# Alimentation.net
KiCad netlist of a schematic drawn in EAGLE
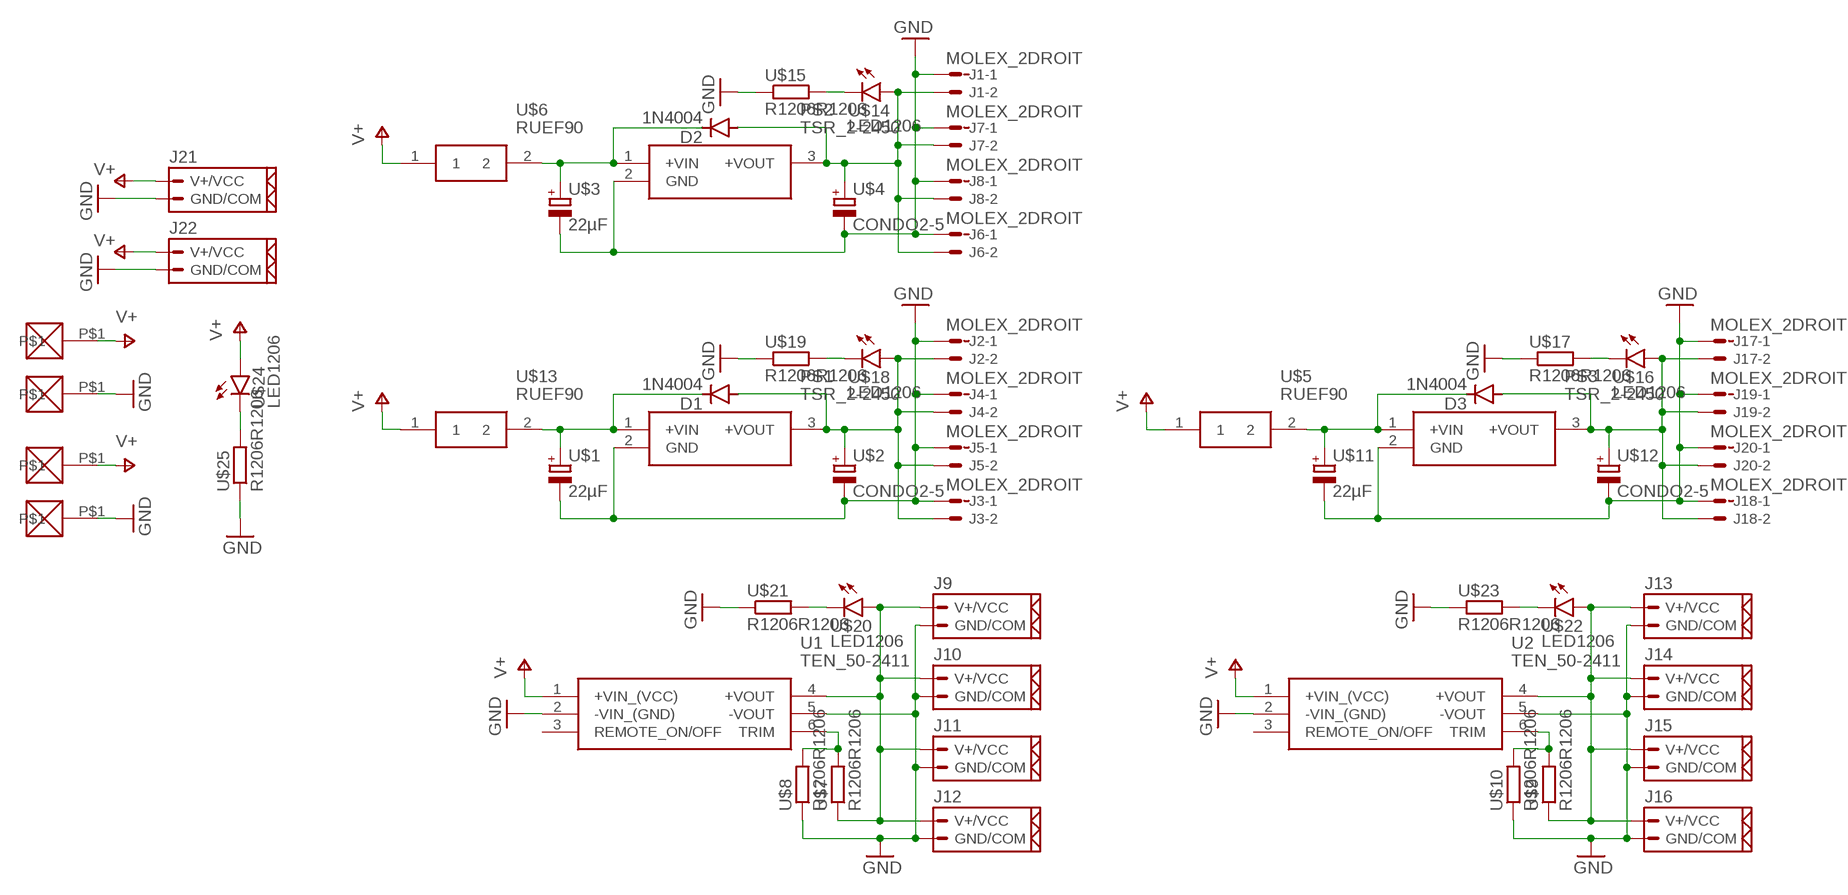
[diagram p0: schematic, sheet 1]

(export (version "E")
  (design (tool "Eeschema 10.0.6"))
  (components
    (comp (ref "D1")
      (value "1N4004")
      (footprint "eagle-import:DO41-10")
      (libsource (lib "eagle-import") (part "1N4004"))
    )
    (comp (ref "D2")
      (value "1N4004")
      (footprint "eagle-import:DO41-10")
      (libsource (lib "eagle-import") (part "1N4004"))
    )
    (comp (ref "D3")
      (value "1N4004")
      (footprint "eagle-import:DO41-10")
      (libsource (lib "eagle-import") (part "1N4004"))
    )
    (comp (ref "J1")
      (value "MOLEX_2DROIT")
      (footprint "eagle-import:CON_2_DROIT")
      (fields (field (name "MF") "MOLEX"))
      (libsource (lib "eagle-import") (part "MOLEX_2DROIT"))
    )
    (comp (ref "J2")
      (value "MOLEX_2DROIT")
      (footprint "eagle-import:CON_2_DROIT")
      (fields (field (name "MF") "MOLEX"))
      (libsource (lib "eagle-import") (part "MOLEX_2DROIT"))
    )
    (comp (ref "J3")
      (value "MOLEX_2DROIT")
      (footprint "eagle-import:CON_2_DROIT")
      (fields (field (name "MF") "MOLEX"))
      (libsource (lib "eagle-import") (part "MOLEX_2DROIT"))
    )
    (comp (ref "J4")
      (value "MOLEX_2DROIT")
      (footprint "eagle-import:CON_2_DROIT")
      (fields (field (name "MF") "MOLEX"))
      (libsource (lib "eagle-import") (part "MOLEX_2DROIT"))
    )
    (comp (ref "J5")
      (value "MOLEX_2DROIT")
      (footprint "eagle-import:CON_2_DROIT")
      (fields (field (name "MF") "MOLEX"))
      (libsource (lib "eagle-import") (part "MOLEX_2DROIT"))
    )
    (comp (ref "J6")
      (value "MOLEX_2DROIT")
      (footprint "eagle-import:CON_2_DROIT")
      (fields (field (name "MF") "MOLEX"))
      (libsource (lib "eagle-import") (part "MOLEX_2DROIT"))
    )
    (comp (ref "J7")
      (value "MOLEX_2DROIT")
      (footprint "eagle-import:CON_2_DROIT")
      (fields (field (name "MF") "MOLEX"))
      (libsource (lib "eagle-import") (part "MOLEX_2DROIT"))
    )
    (comp (ref "J8")
      (value "MOLEX_2DROIT")
      (footprint "eagle-import:CON_2_DROIT")
      (fields (field (name "MF") "MOLEX"))
      (libsource (lib "eagle-import") (part "MOLEX_2DROIT"))
    )
    (comp (ref "J9")
      (value "MOLEX_2_PUISSDROIT")
      (footprint "eagle-import:CON_2_PUISS_DROIT")
      (libsource (lib "eagle-import") (part "MOLEX_2_PUISSDROIT"))
    )
    (comp (ref "J10")
      (value "MOLEX_2_PUISSDROIT")
      (footprint "eagle-import:CON_2_PUISS_DROIT")
      (libsource (lib "eagle-import") (part "MOLEX_2_PUISSDROIT"))
    )
    (comp (ref "J11")
      (value "MOLEX_2_PUISS90°")
      (footprint "eagle-import:CON_2_PUISS_90°")
      (libsource (lib "eagle-import") (part "MOLEX_2_PUISS90°"))
    )
    (comp (ref "J12")
      (value "MOLEX_2_PUISS90°")
      (footprint "eagle-import:CON_2_PUISS_90°")
      (libsource (lib "eagle-import") (part "MOLEX_2_PUISS90°"))
    )
    (comp (ref "J13")
      (value "MOLEX_2_PUISSDROIT")
      (footprint "eagle-import:CON_2_PUISS_DROIT")
      (libsource (lib "eagle-import") (part "MOLEX_2_PUISSDROIT"))
    )
    (comp (ref "J14")
      (value "MOLEX_2_PUISSDROIT")
      (footprint "eagle-import:CON_2_PUISS_DROIT")
      (libsource (lib "eagle-import") (part "MOLEX_2_PUISSDROIT"))
    )
    (comp (ref "J15")
      (value "MOLEX_2_PUISS90°")
      (footprint "eagle-import:CON_2_PUISS_90°")
      (libsource (lib "eagle-import") (part "MOLEX_2_PUISS90°"))
    )
    (comp (ref "J16")
      (value "MOLEX_2_PUISS90°")
      (footprint "eagle-import:CON_2_PUISS_90°")
      (libsource (lib "eagle-import") (part "MOLEX_2_PUISS90°"))
    )
    (comp (ref "J17")
      (value "MOLEX_2DROIT")
      (footprint "eagle-import:CON_2_DROIT")
      (fields (field (name "MF") "MOLEX"))
      (libsource (lib "eagle-import") (part "MOLEX_2DROIT"))
    )
    (comp (ref "J18")
      (value "MOLEX_2DROIT")
      (footprint "eagle-import:CON_2_DROIT")
      (fields (field (name "MF") "MOLEX"))
      (libsource (lib "eagle-import") (part "MOLEX_2DROIT"))
    )
    (comp (ref "J19")
      (value "MOLEX_2DROIT")
      (footprint "eagle-import:CON_2_DROIT")
      (fields (field (name "MF") "MOLEX"))
      (libsource (lib "eagle-import") (part "MOLEX_2DROIT"))
    )
    (comp (ref "J20")
      (value "MOLEX_2DROIT")
      (footprint "eagle-import:CON_2_DROIT")
      (fields (field (name "MF") "MOLEX"))
      (libsource (lib "eagle-import") (part "MOLEX_2DROIT"))
    )
    (comp (ref "J21")
      (value "MOLEX_2_PUISS90°")
      (footprint "eagle-import:CON_2_PUISS_90°")
      (libsource (lib "eagle-import") (part "MOLEX_2_PUISS90°"))
    )
    (comp (ref "J22")
      (value "MOLEX_2_PUISS90°")
      (footprint "eagle-import:CON_2_PUISS_90°")
      (libsource (lib "eagle-import") (part "MOLEX_2_PUISS90°"))
    )
    (comp (ref "PS1")
      (value "TSR_2-2450")
      (footprint "eagle-import:TSR-2")
      (fields
        (field (name "MANUFACTURER_PART_NUMBER") "TSR 2-2450")
        (field (name "MOUSER_PART_NUMBER") "495-TSR2-2450")
        (field (name "RS_PART_NUMBER") "1666063")
      )
      (libsource (lib "eagle-import") (part "TSR_2-2450"))
    )
    (comp (ref "PS2")
      (value "TSR_2-2450")
      (footprint "eagle-import:TSR-2")
      (fields
        (field (name "MANUFACTURER_PART_NUMBER") "TSR 2-2450")
        (field (name "MOUSER_PART_NUMBER") "495-TSR2-2450")
        (field (name "RS_PART_NUMBER") "1666063")
      )
      (libsource (lib "eagle-import") (part "TSR_2-2450"))
    )
    (comp (ref "PS3")
      (value "TSR_2-2450")
      (footprint "eagle-import:TSR-2")
      (fields
        (field (name "MANUFACTURER_PART_NUMBER") "TSR 2-2450")
        (field (name "MOUSER_PART_NUMBER") "495-TSR2-2450")
        (field (name "RS_PART_NUMBER") "1666063")
      )
      (libsource (lib "eagle-import") (part "TSR_2-2450"))
    )
    (comp (ref "U$1")
      (value "22µF")
      (footprint "eagle-import:E2-5")
      (libsource (lib "eagle-import") (part "CONDO2-5"))
    )
    (comp (ref "U$2")
      (value "CONDO2-5")
      (footprint "eagle-import:E2-5")
      (libsource (lib "eagle-import") (part "CONDO2-5"))
    )
    (comp (ref "U$3")
      (value "22µF")
      (footprint "eagle-import:E2-5")
      (libsource (lib "eagle-import") (part "CONDO2-5"))
    )
    (comp (ref "U$4")
      (value "CONDO2-5")
      (footprint "eagle-import:E2-5")
      (libsource (lib "eagle-import") (part "CONDO2-5"))
    )
    (comp (ref "U$5")
      (value "RUEF90")
      (footprint "eagle-import:RUEF090")
      (libsource (lib "eagle-import") (part "RUEF90"))
    )
    (comp (ref "U$6")
      (value "RUEF90")
      (footprint "eagle-import:RUEF090")
      (libsource (lib "eagle-import") (part "RUEF90"))
    )
    (comp (ref "U$7")
      (value "R1206R1206")
      (footprint "eagle-import:R1206")
      (libsource (lib "eagle-import") (part "R1206R1206"))
    )
    (comp (ref "U$8")
      (value "R1206R1206")
      (footprint "eagle-import:R1206")
      (libsource (lib "eagle-import") (part "R1206R1206"))
    )
    (comp (ref "U$9")
      (value "R1206R1206")
      (footprint "eagle-import:R1206")
      (libsource (lib "eagle-import") (part "R1206R1206"))
    )
    (comp (ref "U$10")
      (value "R1206R1206")
      (footprint "eagle-import:R1206")
      (libsource (lib "eagle-import") (part "R1206R1206"))
    )
    (comp (ref "U$11")
      (value "22µF")
      (footprint "eagle-import:E2-5")
      (libsource (lib "eagle-import") (part "CONDO2-5"))
    )
    (comp (ref "U$12")
      (value "CONDO2-5")
      (footprint "eagle-import:E2-5")
      (libsource (lib "eagle-import") (part "CONDO2-5"))
    )
    (comp (ref "U$13")
      (value "RUEF90")
      (footprint "eagle-import:RUEF090")
      (libsource (lib "eagle-import") (part "RUEF90"))
    )
    (comp (ref "U$14")
      (value "LED1206")
      (footprint "eagle-import:1206")
      (libsource (lib "eagle-import") (part "LED1206"))
    )
    (comp (ref "U$15")
      (value "R1206R1206")
      (footprint "eagle-import:R1206")
      (libsource (lib "eagle-import") (part "R1206R1206"))
    )
    (comp (ref "U$16")
      (value "LED1206")
      (footprint "eagle-import:1206")
      (libsource (lib "eagle-import") (part "LED1206"))
    )
    (comp (ref "U$17")
      (value "R1206R1206")
      (footprint "eagle-import:R1206")
      (libsource (lib "eagle-import") (part "R1206R1206"))
    )
    (comp (ref "U$18")
      (value "LED1206")
      (footprint "eagle-import:1206")
      (libsource (lib "eagle-import") (part "LED1206"))
    )
    (comp (ref "U$19")
      (value "R1206R1206")
      (footprint "eagle-import:R1206")
      (libsource (lib "eagle-import") (part "R1206R1206"))
    )
    (comp (ref "U$20")
      (value "LED1206")
      (footprint "eagle-import:1206")
      (libsource (lib "eagle-import") (part "LED1206"))
    )
    (comp (ref "U$21")
      (value "R1206R1206")
      (footprint "eagle-import:R1206")
      (libsource (lib "eagle-import") (part "R1206R1206"))
    )
    (comp (ref "U$22")
      (value "LED1206")
      (footprint "eagle-import:1206")
      (libsource (lib "eagle-import") (part "LED1206"))
    )
    (comp (ref "U$23")
      (value "R1206R1206")
      (footprint "eagle-import:R1206")
      (libsource (lib "eagle-import") (part "R1206R1206"))
    )
    (comp (ref "U$24")
      (value "LED1206")
      (footprint "eagle-import:1206")
      (libsource (lib "eagle-import") (part "LED1206"))
    )
    (comp (ref "U$25")
      (value "R1206R1206")
      (footprint "eagle-import:R1206")
      (libsource (lib "eagle-import") (part "R1206R1206"))
    )
    (comp (ref "U$26")
      (value "BAT_WIRE_SOLD")
      (footprint "eagle-import:LARGE_PAD_BATT")
      (libsource (lib "eagle-import") (part "BAT_WIRE_SOLD"))
    )
    (comp (ref "U$27")
      (value "BAT_WIRE_SOLD")
      (footprint "eagle-import:LARGE_PAD_BATT")
      (libsource (lib "eagle-import") (part "BAT_WIRE_SOLD"))
    )
    (comp (ref "U$28")
      (value "BAT_WIRE_SOLD")
      (footprint "eagle-import:LARGE_PAD_BATT")
      (libsource (lib "eagle-import") (part "BAT_WIRE_SOLD"))
    )
    (comp (ref "U$29")
      (value "BAT_WIRE_SOLD")
      (footprint "eagle-import:LARGE_PAD_BATT")
      (libsource (lib "eagle-import") (part "BAT_WIRE_SOLD"))
    )
    (comp (ref "U1")
      (value "TEN_50-2411")
      (footprint "eagle-import:TEN_50-2411")
      (fields
        (field (name "MANUFACTURER_PART_NUMBER") "TEN 50-2411")
        (field (name "RS_PART_NUMBER") "7702299")
      )
      (libsource (lib "eagle-import") (part "TEN_50-2411"))
    )
    (comp (ref "U2")
      (value "TEN_50-2411")
      (footprint "eagle-import:TEN_50-2411")
      (fields
        (field (name "MANUFACTURER_PART_NUMBER") "TEN 50-2411")
        (field (name "RS_PART_NUMBER") "7702299")
      )
      (libsource (lib "eagle-import") (part "TEN_50-2411"))
    )
  )
  (nets
    (net (code "1") (name "GND") (class "Default")
      (node (ref "J1") (pin "1") (pinfunction "S_1") (pintype "passive"))
      (node (ref "J10") (pin "1") (pinfunction "GND/COM_1") (pintype "passive"))
      (node (ref "J11") (pin "P$1") (pinfunction "GND/COM_P$1") (pintype "passive"))
      (node (ref "J12") (pin "P$1") (pinfunction "GND/COM_P$1") (pintype "passive"))
      (node (ref "J13") (pin "1") (pinfunction "GND/COM_1") (pintype "passive"))
      (node (ref "J14") (pin "1") (pinfunction "GND/COM_1") (pintype "passive"))
      (node (ref "J15") (pin "P$1") (pinfunction "GND/COM_P$1") (pintype "passive"))
      (node (ref "J16") (pin "P$1") (pinfunction "GND/COM_P$1") (pintype "passive"))
      (node (ref "J17") (pin "1") (pinfunction "S_1") (pintype "passive"))
      (node (ref "J18") (pin "1") (pinfunction "S_1") (pintype "passive"))
      (node (ref "J19") (pin "1") (pinfunction "S_1") (pintype "passive"))
      (node (ref "J2") (pin "1") (pinfunction "S_1") (pintype "passive"))
      (node (ref "J20") (pin "1") (pinfunction "S_1") (pintype "passive"))
      (node (ref "J21") (pin "P$1") (pinfunction "GND/COM_P$1") (pintype "passive"))
      (node (ref "J22") (pin "P$1") (pinfunction "GND/COM_P$1") (pintype "passive"))
      (node (ref "J3") (pin "1") (pinfunction "S_1") (pintype "passive"))
      (node (ref "J4") (pin "1") (pinfunction "S_1") (pintype "passive"))
      (node (ref "J5") (pin "1") (pinfunction "S_1") (pintype "passive"))
      (node (ref "J6") (pin "1") (pinfunction "S_1") (pintype "passive"))
      (node (ref "J7") (pin "1") (pinfunction "S_1") (pintype "passive"))
      (node (ref "J8") (pin "1") (pinfunction "S_1") (pintype "passive"))
      (node (ref "J9") (pin "1") (pinfunction "GND/COM_1") (pintype "passive"))
      (node (ref "PS1") (pin "2") (pinfunction "GND_2") (pintype "power_in"))
      (node (ref "PS2") (pin "2") (pinfunction "GND_2") (pintype "power_in"))
      (node (ref "PS3") (pin "2") (pinfunction "GND_2") (pintype "power_in"))
      (node (ref "U$1") (pin "-") (pinfunction "-_-") (pintype "passive"))
      (node (ref "U$10") (pin "1") (pinfunction "1_1") (pintype "passive"))
      (node (ref "U$11") (pin "-") (pinfunction "-_-") (pintype "passive"))
      (node (ref "U$12") (pin "-") (pinfunction "-_-") (pintype "passive"))
      (node (ref "U$15") (pin "1") (pinfunction "1_1") (pintype "passive"))
      (node (ref "U$17") (pin "1") (pinfunction "1_1") (pintype "passive"))
      (node (ref "U$19") (pin "1") (pinfunction "1_1") (pintype "passive"))
      (node (ref "U$2") (pin "-") (pinfunction "-_-") (pintype "passive"))
      (node (ref "U$21") (pin "1") (pinfunction "1_1") (pintype "passive"))
      (node (ref "U$23") (pin "1") (pinfunction "1_1") (pintype "passive"))
      (node (ref "U$25") (pin "1") (pinfunction "1_1") (pintype "passive"))
      (node (ref "U$26") (pin "P$1") (pinfunction "P$1_P$1") (pintype "bidirectional"))
      (node (ref "U$28") (pin "P$1") (pinfunction "P$1_P$1") (pintype "bidirectional"))
      (node (ref "U$3") (pin "-") (pinfunction "-_-") (pintype "passive"))
      (node (ref "U$4") (pin "-") (pinfunction "-_-") (pintype "passive"))
      (node (ref "U$8") (pin "1") (pinfunction "1_1") (pintype "passive"))
      (node (ref "U1") (pin "2") (pinfunction "-VIN_(GND)_2") (pintype "input"))
      (node (ref "U1") (pin "5") (pinfunction "-VOUT_5") (pintype "input"))
      (node (ref "U2") (pin "2") (pinfunction "-VIN_(GND)_2") (pintype "input"))
      (node (ref "U2") (pin "5") (pinfunction "-VOUT_5") (pintype "input"))
    )
    (net (code "2") (name "Net-(J1B-S)") (class "Default")
      (node (ref "D2") (pin "A") (pinfunction "A_A") (pintype "passive"))
      (node (ref "J1") (pin "2") (pinfunction "S_2") (pintype "passive"))
      (node (ref "J6") (pin "2") (pinfunction "S_2") (pintype "passive"))
      (node (ref "J7") (pin "2") (pinfunction "S_2") (pintype "passive"))
      (node (ref "J8") (pin "2") (pinfunction "S_2") (pintype "passive"))
      (node (ref "PS2") (pin "3") (pinfunction "+VOUT_3") (pintype "output"))
      (node (ref "U$14") (pin "A") (pinfunction "A_A") (pintype "passive"))
      (node (ref "U$4") (pin "+") (pinfunction "+_+") (pintype "passive"))
    )
    (net (code "3") (name "Net-(J2B-S)") (class "Default")
      (node (ref "D1") (pin "A") (pinfunction "A_A") (pintype "passive"))
      (node (ref "J2") (pin "2") (pinfunction "S_2") (pintype "passive"))
      (node (ref "J3") (pin "2") (pinfunction "S_2") (pintype "passive"))
      (node (ref "J4") (pin "2") (pinfunction "S_2") (pintype "passive"))
      (node (ref "J5") (pin "2") (pinfunction "S_2") (pintype "passive"))
      (node (ref "PS1") (pin "3") (pinfunction "+VOUT_3") (pintype "output"))
      (node (ref "U$18") (pin "A") (pinfunction "A_A") (pintype "passive"))
      (node (ref "U$2") (pin "+") (pinfunction "+_+") (pintype "passive"))
    )
    (net (code "4") (name "Net-(J10-V+{slash}VCC)") (class "Default")
      (node (ref "J10") (pin "2") (pinfunction "V+/VCC_2") (pintype "passive"))
      (node (ref "J11") (pin "P$2") (pinfunction "V+/VCC_P$2") (pintype "passive"))
      (node (ref "J12") (pin "P$2") (pinfunction "V+/VCC_P$2") (pintype "passive"))
      (node (ref "J9") (pin "2") (pinfunction "V+/VCC_2") (pintype "passive"))
      (node (ref "U$20") (pin "A") (pinfunction "A_A") (pintype "passive"))
      (node (ref "U$7") (pin "1") (pinfunction "1_1") (pintype "passive"))
      (node (ref "U1") (pin "4") (pinfunction "+VOUT_4") (pintype "input"))
    )
    (net (code "5") (name "Net-(J13-V+{slash}VCC)") (class "Default")
      (node (ref "J13") (pin "2") (pinfunction "V+/VCC_2") (pintype "passive"))
      (node (ref "J14") (pin "2") (pinfunction "V+/VCC_2") (pintype "passive"))
      (node (ref "J15") (pin "P$2") (pinfunction "V+/VCC_P$2") (pintype "passive"))
      (node (ref "J16") (pin "P$2") (pinfunction "V+/VCC_P$2") (pintype "passive"))
      (node (ref "U$22") (pin "A") (pinfunction "A_A") (pintype "passive"))
      (node (ref "U$9") (pin "1") (pinfunction "1_1") (pintype "passive"))
      (node (ref "U2") (pin "4") (pinfunction "+VOUT_4") (pintype "input"))
    )
    (net (code "6") (name "Net-(J17B-S)") (class "Default")
      (node (ref "D3") (pin "A") (pinfunction "A_A") (pintype "passive"))
      (node (ref "J17") (pin "2") (pinfunction "S_2") (pintype "passive"))
      (node (ref "J18") (pin "2") (pinfunction "S_2") (pintype "passive"))
      (node (ref "J19") (pin "2") (pinfunction "S_2") (pintype "passive"))
      (node (ref "J20") (pin "2") (pinfunction "S_2") (pintype "passive"))
      (node (ref "PS3") (pin "3") (pinfunction "+VOUT_3") (pintype "output"))
      (node (ref "U$12") (pin "+") (pinfunction "+_+") (pintype "passive"))
      (node (ref "U$16") (pin "A") (pinfunction "A_A") (pintype "passive"))
    )
    (net (code "7") (name "Net-(PS1-+VIN)") (class "Default")
      (node (ref "D1") (pin "C") (pinfunction "C_C") (pintype "passive"))
      (node (ref "PS1") (pin "1") (pinfunction "+VIN_1") (pintype "input"))
      (node (ref "U$1") (pin "+") (pinfunction "+_+") (pintype "passive"))
      (node (ref "U$13") (pin "2") (pinfunction "2_2") (pintype "bidirectional"))
    )
    (net (code "8") (name "Net-(PS2-+VIN)") (class "Default")
      (node (ref "D2") (pin "C") (pinfunction "C_C") (pintype "passive"))
      (node (ref "PS2") (pin "1") (pinfunction "+VIN_1") (pintype "input"))
      (node (ref "U$3") (pin "+") (pinfunction "+_+") (pintype "passive"))
      (node (ref "U$6") (pin "2") (pinfunction "2_2") (pintype "bidirectional"))
    )
    (net (code "9") (name "Net-(PS3-+VIN)") (class "Default")
      (node (ref "D3") (pin "C") (pinfunction "C_C") (pintype "passive"))
      (node (ref "PS3") (pin "1") (pinfunction "+VIN_1") (pintype "input"))
      (node (ref "U$11") (pin "+") (pinfunction "+_+") (pintype "passive"))
      (node (ref "U$5") (pin "2") (pinfunction "2_2") (pintype "bidirectional"))
    )
    (net (code "10") (name "Net-(U$14-PadC)") (class "Default")
      (node (ref "U$14") (pin "C") (pinfunction "C_C") (pintype "passive"))
      (node (ref "U$15") (pin "2") (pinfunction "2_2") (pintype "passive"))
    )
    (net (code "11") (name "Net-(U$16-PadC)") (class "Default")
      (node (ref "U$16") (pin "C") (pinfunction "C_C") (pintype "passive"))
      (node (ref "U$17") (pin "2") (pinfunction "2_2") (pintype "passive"))
    )
    (net (code "12") (name "Net-(U$18-PadC)") (class "Default")
      (node (ref "U$18") (pin "C") (pinfunction "C_C") (pintype "passive"))
      (node (ref "U$19") (pin "2") (pinfunction "2_2") (pintype "passive"))
    )
    (net (code "13") (name "Net-(U$20-PadC)") (class "Default")
      (node (ref "U$20") (pin "C") (pinfunction "C_C") (pintype "passive"))
      (node (ref "U$21") (pin "2") (pinfunction "2_2") (pintype "passive"))
    )
    (net (code "14") (name "Net-(U$22-PadC)") (class "Default")
      (node (ref "U$22") (pin "C") (pinfunction "C_C") (pintype "passive"))
      (node (ref "U$23") (pin "2") (pinfunction "2_2") (pintype "passive"))
    )
    (net (code "15") (name "Net-(U$24-PadC)") (class "Default")
      (node (ref "U$24") (pin "C") (pinfunction "C_C") (pintype "passive"))
      (node (ref "U$25") (pin "2") (pinfunction "2_2") (pintype "passive"))
    )
    (net (code "16") (name "Net-(U1-TRIM)") (class "Default")
      (node (ref "U$7") (pin "2") (pinfunction "2_2") (pintype "passive"))
      (node (ref "U$8") (pin "2") (pinfunction "2_2") (pintype "passive"))
      (node (ref "U1") (pin "6") (pinfunction "TRIM_6") (pintype "input"))
    )
    (net (code "17") (name "Net-(U2-TRIM)") (class "Default")
      (node (ref "U$10") (pin "2") (pinfunction "2_2") (pintype "passive"))
      (node (ref "U$9") (pin "2") (pinfunction "2_2") (pintype "passive"))
      (node (ref "U2") (pin "6") (pinfunction "TRIM_6") (pintype "input"))
    )
    (net (code "18") (name "V+") (class "Default")
      (node (ref "J21") (pin "P$2") (pinfunction "V+/VCC_P$2") (pintype "passive"))
      (node (ref "J22") (pin "P$2") (pinfunction "V+/VCC_P$2") (pintype "passive"))
      (node (ref "U$13") (pin "1") (pinfunction "1_1") (pintype "bidirectional"))
      (node (ref "U$24") (pin "A") (pinfunction "A_A") (pintype "passive"))
      (node (ref "U$27") (pin "P$1") (pinfunction "P$1_P$1") (pintype "bidirectional"))
      (node (ref "U$29") (pin "P$1") (pinfunction "P$1_P$1") (pintype "bidirectional"))
      (node (ref "U$5") (pin "1") (pinfunction "1_1") (pintype "bidirectional"))
      (node (ref "U$6") (pin "1") (pinfunction "1_1") (pintype "bidirectional"))
      (node (ref "U1") (pin "1") (pinfunction "+VIN_(VCC)_1") (pintype "input"))
      (node (ref "U2") (pin "1") (pinfunction "+VIN_(VCC)_1") (pintype "input"))
    )
    (net (code "19") (name "unconnected-(U1-REMOTE_ON{slash}OFF-Pad3)") (class "Default")
      (node (ref "U1") (pin "3") (pinfunction "REMOTE_ON/OFF_3") (pintype "input"))
    )
    (net (code "20") (name "unconnected-(U2-REMOTE_ON{slash}OFF-Pad3)") (class "Default")
      (node (ref "U2") (pin "3") (pinfunction "REMOTE_ON/OFF_3") (pintype "input"))
    )
  )
)
